# ProtoSnap-LilyTwinkle.net
KiCad netlist of a schematic drawn in EAGLE
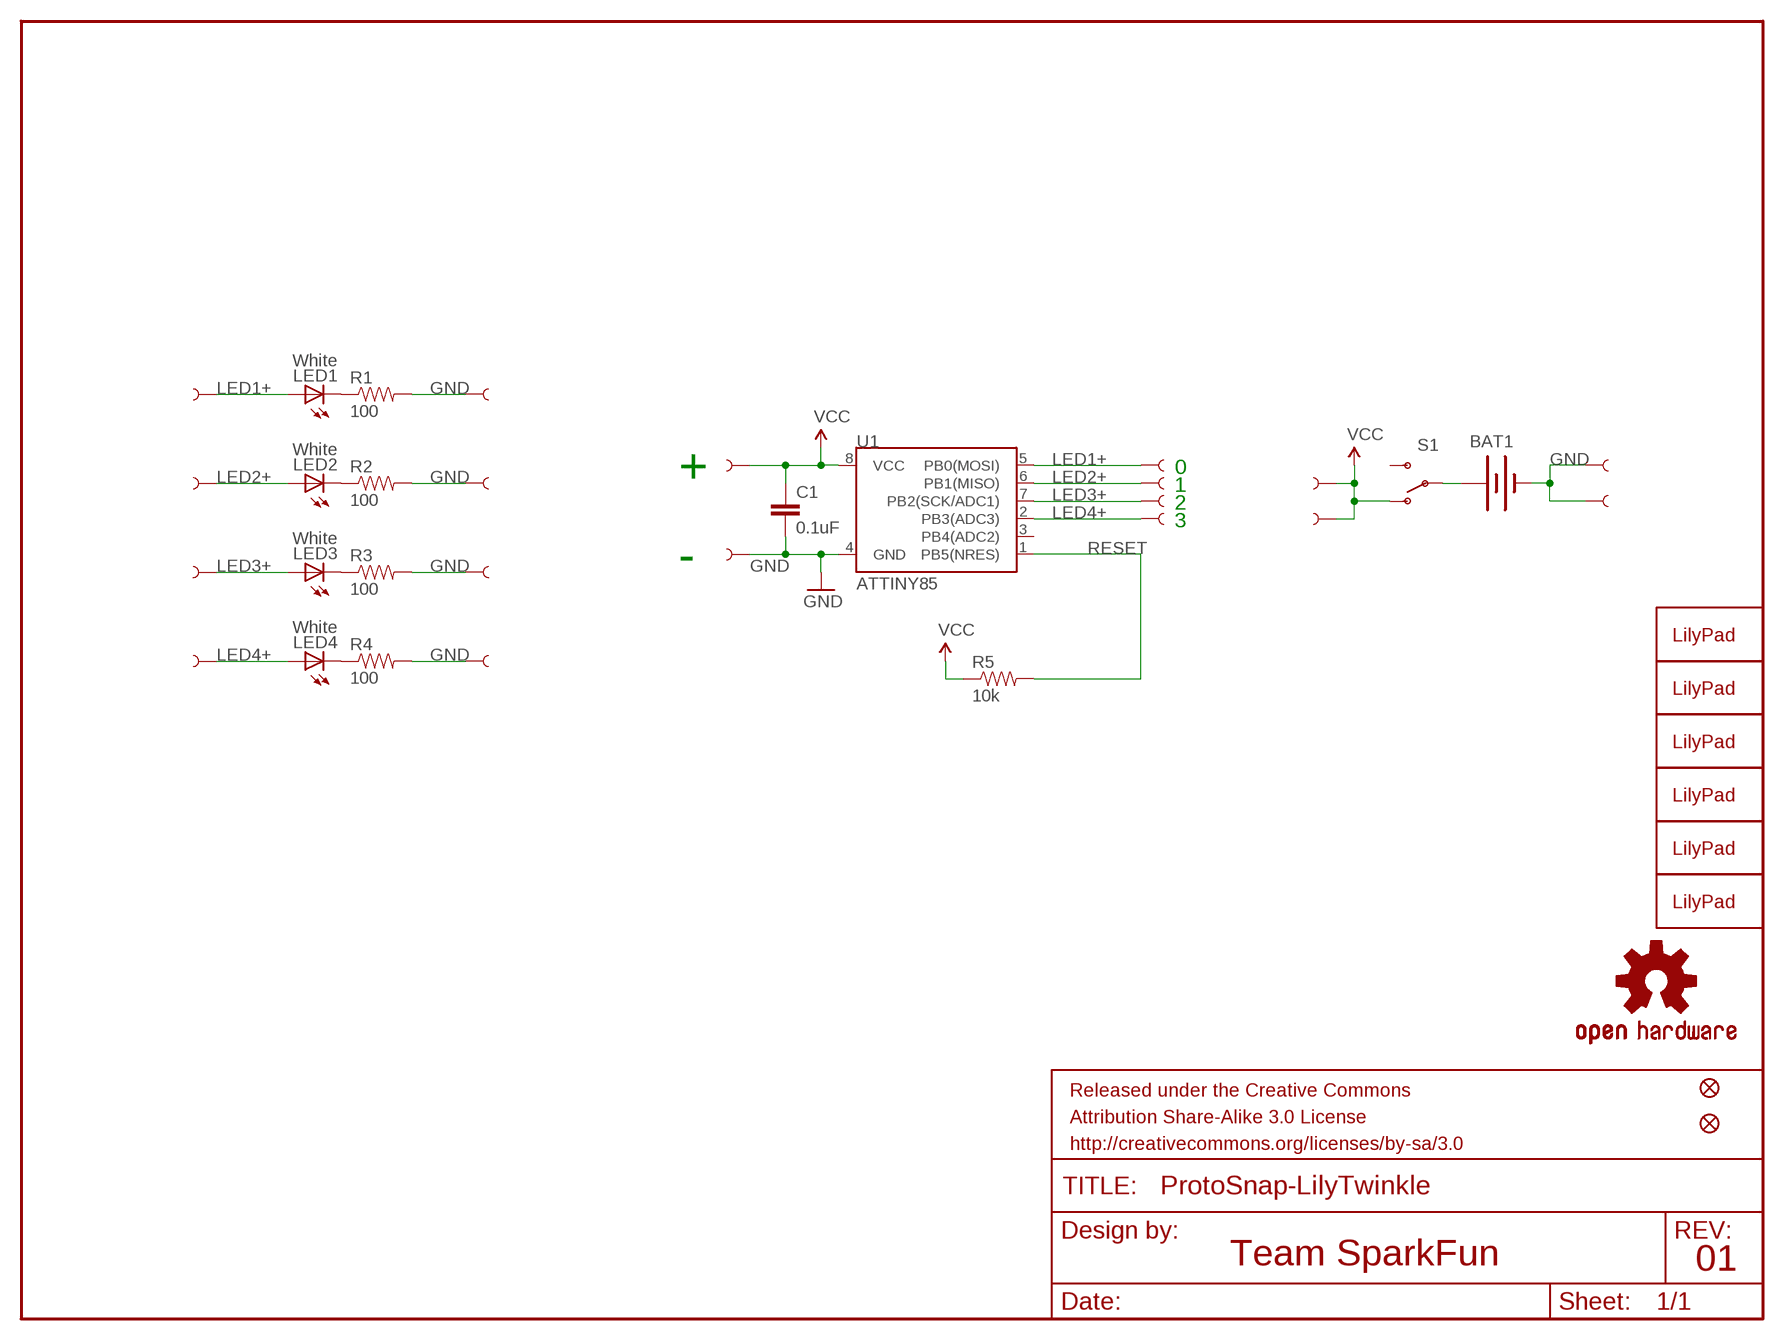
[diagram p0: schematic, sheet 1]

(export (version "E")
  (design (tool "Eeschema 10.0.6"))
  (components
    (comp (ref "1_U$2")
      (value "SEWTAP6")
      (footprint "eagle-import:PETAL-SMALL-2SIDE")
      (libsource (lib "eagle-import") (part "SEWTAP6"))
    )
    (comp (ref "1_U$3")
      (value "SEWTAP6")
      (footprint "eagle-import:PETAL-SMALL-2SIDE")
      (libsource (lib "eagle-import") (part "SEWTAP6"))
    )
    (comp (ref "1_U$4")
      (value "SEWTAP6")
      (footprint "eagle-import:PETAL-SMALL-2SIDE")
      (libsource (lib "eagle-import") (part "SEWTAP6"))
    )
    (comp (ref "1_U$5")
      (value "SEWTAP6")
      (footprint "eagle-import:PETAL-SMALL-2SIDE")
      (libsource (lib "eagle-import") (part "SEWTAP6"))
    )
    (comp (ref "1_U$6")
      (value "SEWTAP6")
      (footprint "eagle-import:PETAL-SMALL-2SIDE")
      (libsource (lib "eagle-import") (part "SEWTAP6"))
    )
    (comp (ref "1_U$7")
      (value "SEWTAP6")
      (footprint "eagle-import:PETAL-SMALL-2SIDE")
      (libsource (lib "eagle-import") (part "SEWTAP6"))
    )
    (comp (ref "3_LED+")
      (value "SEWTAP6")
      (footprint "eagle-import:PETAL-SMALL")
      (libsource (lib "eagle-import") (part "3_LilyPad-Wearables_SEWTAP4"))
    )
    (comp (ref "3_LED-")
      (value "SEWTAP6")
      (footprint "eagle-import:PETAL-SMALL")
      (libsource (lib "eagle-import") (part "SEWTAP2SIDE"))
    )
    (comp (ref "4_LED+")
      (value "SEWTAP6")
      (footprint "eagle-import:PETAL-SMALL")
      (libsource (lib "eagle-import") (part "4_LilyPad-Wearables_SEWTAP4"))
    )
    (comp (ref "4_LED-")
      (value "SEWTAP6")
      (footprint "eagle-import:PETAL-SMALL")
      (libsource (lib "eagle-import") (part "4_LilyPad-Wearables_SEWTAP2SIDE"))
    )
    (comp (ref "5_LED+")
      (value "SEWTAP6")
      (footprint "eagle-import:PETAL-SMALL")
      (libsource (lib "eagle-import") (part "5_LilyPad-Wearables_SEWTAP4"))
    )
    (comp (ref "5_LED-")
      (value "SEWTAP6")
      (footprint "eagle-import:PETAL-SMALL")
      (libsource (lib "eagle-import") (part "5_LilyPad-Wearables_SEWTAP2SIDE"))
    )
    (comp (ref "6_LED+")
      (value "SEWTAP6")
      (footprint "eagle-import:PETAL-SMALL")
      (libsource (lib "eagle-import") (part "6_LilyPad-Wearables_SEWTAP4"))
    )
    (comp (ref "6_LED-")
      (value "SEWTAP6")
      (footprint "eagle-import:PETAL-SMALL")
      (libsource (lib "eagle-import") (part "6_LilyPad-Wearables_SEWTAP2SIDE"))
    )
    (comp (ref "B1+")
      (value "SEWTAP6")
      (footprint "eagle-import:PETAL-SMALL-2SIDE")
      (libsource (lib "eagle-import") (part "2_LilyPad-Wearables_SEWTAP6"))
    )
    (comp (ref "B1-")
      (value "SEWTAP6")
      (footprint "eagle-import:PETAL-SMALL-2SIDE")
      (libsource (lib "eagle-import") (part "2_LilyPad-Wearables_SEWTAP6"))
    )
    (comp (ref "B2+")
      (value "SEWTAP6")
      (footprint "eagle-import:PETAL-SMALL-2SIDE")
      (libsource (lib "eagle-import") (part "2_LilyPad-Wearables_SEWTAP6"))
    )
    (comp (ref "B2-")
      (value "SEWTAP6")
      (footprint "eagle-import:PETAL-SMALL-2SIDE")
      (libsource (lib "eagle-import") (part "2_LilyPad-Wearables_SEWTAP6"))
    )
    (comp (ref "BAT1")
      (value "BATTERY20MM_4LEGS")
      (footprint "eagle-import:BATTCON_20MM_4LEGS")
      (libsource (lib "eagle-import") (part "BATTERY20MM_4LEGS"))
    )
    (comp (ref "BATT_LOGO")
      (value "LOGO-LPLP")
      (footprint "eagle-import:LOGO-LILYPAD")
      (libsource (lib "eagle-import") (part "LOGO-LPLP"))
    )
    (comp (ref "BATT_OHS")
      (value "OSHW-LOGOS")
      (footprint "eagle-import:OSHW-LOGO-S")
      (libsource (lib "eagle-import") (part "OSHW-LOGOS"))
    )
    (comp (ref "C1")
      (value "0.1uF")
      (footprint "eagle-import:0402-CAP")
      (libsource (lib "eagle-import") (part ".1UF-CER"))
    )
    (comp (ref "FRAME1")
      (value "FRAME-LETTER")
      (footprint "eagle-import:CREATIVE_COMMONS")
      (libsource (lib "eagle-import") (part "FRAME-LETTER"))
    )
    (comp (ref "JP1")
      (value "FIDUCIALUFIDUCIAL")
      (footprint "eagle-import:MICRO-FIDUCIAL")
      (libsource (lib "eagle-import") (part "FIDUCIALUFIDUCIAL"))
    )
    (comp (ref "JP2")
      (value "FIDUCIALUFIDUCIAL")
      (footprint "eagle-import:MICRO-FIDUCIAL")
      (libsource (lib "eagle-import") (part "FIDUCIALUFIDUCIAL"))
    )
    (comp (ref "LED1")
      (value "White")
      (footprint "eagle-import:LED-1206")
      (libsource (lib "eagle-import") (part "LED-WHITE"))
    )
    (comp (ref "LED1_LOGO")
      (value "LOGO-LPL")
      (footprint "eagle-import:LOGO-L")
      (libsource (lib "eagle-import") (part "LOGO-LPL"))
    )
    (comp (ref "LED2")
      (value "White")
      (footprint "eagle-import:LED-1206")
      (libsource (lib "eagle-import") (part "LED-WHITE"))
    )
    (comp (ref "LED2_LOGO")
      (value "LOGO-LPL")
      (footprint "eagle-import:LOGO-L")
      (libsource (lib "eagle-import") (part "LOGO-LPL"))
    )
    (comp (ref "LED3")
      (value "White")
      (footprint "eagle-import:LED-1206")
      (libsource (lib "eagle-import") (part "LED-WHITE"))
    )
    (comp (ref "LED3_LOGO")
      (value "LOGO-LPL")
      (footprint "eagle-import:LOGO-L")
      (libsource (lib "eagle-import") (part "LOGO-LPL"))
    )
    (comp (ref "LED4")
      (value "White")
      (footprint "eagle-import:LED-1206")
      (libsource (lib "eagle-import") (part "LED-WHITE"))
    )
    (comp (ref "LED4_LOGO")
      (value "LOGO-LPL")
      (footprint "eagle-import:LOGO-L")
      (libsource (lib "eagle-import") (part "LOGO-LPL"))
    )
    (comp (ref "R1")
      (value "100")
      (footprint "eagle-import:0603-RES")
      (libsource (lib "eagle-import") (part "6_SparkFun_RESISTOR0603-RES"))
    )
    (comp (ref "R2")
      (value "100")
      (footprint "eagle-import:0603-RES")
      (libsource (lib "eagle-import") (part "5_SparkFun_RESISTOR0603-RES"))
    )
    (comp (ref "R3")
      (value "100")
      (footprint "eagle-import:0603-RES")
      (libsource (lib "eagle-import") (part "RESISTOR0603-RES"))
    )
    (comp (ref "R4")
      (value "100")
      (footprint "eagle-import:0603-RES")
      (libsource (lib "eagle-import") (part "4_SparkFun_RESISTOR0603-RES"))
    )
    (comp (ref "R5")
      (value "10k")
      (footprint "eagle-import:0402-RES")
      (libsource (lib "eagle-import") (part "10K-1%RES-00824"))
    )
    (comp (ref "S1")
      (value "SWITCH-SPDTSMD")
      (footprint "eagle-import:AYZ0202")
      (libsource (lib "eagle-import") (part "SWITCH-SPDTSMD"))
    )
    (comp (ref "TINY_LOGO")
      (value "LOGO-LPL")
      (footprint "eagle-import:LOGO-L")
      (libsource (lib "eagle-import") (part "LOGO-LPL"))
    )
    (comp (ref "U1")
      (value "ATTINY85")
      (footprint "eagle-import:SO08-EIAJ")
      (libsource (lib "eagle-import") (part "ATTINY45TINY85-20-SMT"))
    )
  )
  (nets
    (net (code "1") (name "/LED1+") (class "Default")
      (node (ref "1_U$7") (pin "1") (pinfunction "1_1") (pintype "bidirectional"))
      (node (ref "6_LED+") (pin "1") (pinfunction "1_1") (pintype "bidirectional"))
      (node (ref "LED1") (pin "A") (pinfunction "A_A") (pintype "passive"))
      (node (ref "U1") (pin "5") (pinfunction "PB0(MOSI)_5") (pintype "bidirectional"))
    )
    (net (code "2") (name "/LED2+") (class "Default")
      (node (ref "1_U$3") (pin "1") (pinfunction "1_1") (pintype "bidirectional"))
      (node (ref "5_LED+") (pin "1") (pinfunction "1_1") (pintype "bidirectional"))
      (node (ref "LED2") (pin "A") (pinfunction "A_A") (pintype "passive"))
      (node (ref "U1") (pin "6") (pinfunction "PB1(MISO)_6") (pintype "bidirectional"))
    )
    (net (code "3") (name "/LED3+") (class "Default")
      (node (ref "1_U$4") (pin "1") (pinfunction "1_1") (pintype "bidirectional"))
      (node (ref "3_LED+") (pin "1") (pinfunction "1_1") (pintype "bidirectional"))
      (node (ref "LED3") (pin "A") (pinfunction "A_A") (pintype "passive"))
      (node (ref "U1") (pin "7") (pinfunction "PB2(SCK/ADC1)_7") (pintype "bidirectional"))
    )
    (net (code "4") (name "/LED4+") (class "Default")
      (node (ref "1_U$6") (pin "1") (pinfunction "1_1") (pintype "bidirectional"))
      (node (ref "4_LED+") (pin "1") (pinfunction "1_1") (pintype "bidirectional"))
      (node (ref "LED4") (pin "A") (pinfunction "A_A") (pintype "passive"))
      (node (ref "U1") (pin "2") (pinfunction "PB3(ADC3)_2") (pintype "bidirectional"))
    )
    (net (code "5") (name "/RESET") (class "Default")
      (node (ref "R5") (pin "2") (pinfunction "2_2") (pintype "passive"))
      (node (ref "U1") (pin "1") (pinfunction "PB5(NRES)_1") (pintype "bidirectional"))
    )
    (net (code "6") (name "GND") (class "Default")
      (node (ref "1_U$2") (pin "1") (pinfunction "1_1") (pintype "bidirectional"))
      (node (ref "3_LED-") (pin "1") (pinfunction "1_1") (pintype "bidirectional"))
      (node (ref "4_LED-") (pin "1") (pinfunction "1_1") (pintype "bidirectional"))
      (node (ref "5_LED-") (pin "1") (pinfunction "1_1") (pintype "bidirectional"))
      (node (ref "6_LED-") (pin "1") (pinfunction "1_1") (pintype "bidirectional"))
      (node (ref "B1-") (pin "1") (pinfunction "1_1") (pintype "bidirectional"))
      (node (ref "B2-") (pin "1") (pinfunction "1_1") (pintype "bidirectional"))
      (node (ref "BAT1") (pin "2") (pinfunction "-_2") (pintype "power_in"))
      (node (ref "C1") (pin "2") (pinfunction "2_2") (pintype "passive"))
      (node (ref "R1") (pin "2") (pinfunction "2_2") (pintype "passive"))
      (node (ref "R2") (pin "2") (pinfunction "2_2") (pintype "passive"))
      (node (ref "R3") (pin "2") (pinfunction "2_2") (pintype "passive"))
      (node (ref "R4") (pin "2") (pinfunction "2_2") (pintype "passive"))
      (node (ref "U1") (pin "4") (pinfunction "GND_4") (pintype "bidirectional"))
    )
    (net (code "7") (name "Net-(BAT1-+)") (class "Default")
      (node (ref "BAT1") (pin "1") (pinfunction "+_1") (pintype "power_in"))
      (node (ref "S1") (pin "2") (pinfunction "P_2") (pintype "passive"))
    )
    (net (code "8") (name "Net-(LED1-PadC)") (class "Default")
      (node (ref "LED1") (pin "C") (pinfunction "C_C") (pintype "passive"))
      (node (ref "R1") (pin "1") (pinfunction "1_1") (pintype "passive"))
    )
    (net (code "9") (name "Net-(LED2-PadC)") (class "Default")
      (node (ref "LED2") (pin "C") (pinfunction "C_C") (pintype "passive"))
      (node (ref "R2") (pin "1") (pinfunction "1_1") (pintype "passive"))
    )
    (net (code "10") (name "Net-(LED3-PadC)") (class "Default")
      (node (ref "LED3") (pin "C") (pinfunction "C_C") (pintype "passive"))
      (node (ref "R3") (pin "1") (pinfunction "1_1") (pintype "passive"))
    )
    (net (code "11") (name "Net-(LED4-PadC)") (class "Default")
      (node (ref "LED4") (pin "C") (pinfunction "C_C") (pintype "passive"))
      (node (ref "R4") (pin "1") (pinfunction "1_1") (pintype "passive"))
    )
    (net (code "12") (name "VCC") (class "Default")
      (node (ref "1_U$5") (pin "1") (pinfunction "1_1") (pintype "bidirectional"))
      (node (ref "B1+") (pin "1") (pinfunction "1_1") (pintype "bidirectional"))
      (node (ref "B2+") (pin "1") (pinfunction "1_1") (pintype "bidirectional"))
      (node (ref "C1") (pin "1") (pinfunction "1_1") (pintype "passive"))
      (node (ref "R5") (pin "1") (pinfunction "1_1") (pintype "passive"))
      (node (ref "S1") (pin "1") (pinfunction "O_1") (pintype "passive"))
      (node (ref "U1") (pin "8") (pinfunction "VCC_8") (pintype "bidirectional"))
    )
    (net (code "13") (name "unconnected-(S1-S-Pad3)") (class "Default")
      (node (ref "S1") (pin "3") (pinfunction "S_3") (pintype "passive"))
    )
    (net (code "14") (name "unconnected-(U1-PB4(ADC2)-Pad3)") (class "Default")
      (node (ref "U1") (pin "3") (pinfunction "PB4(ADC2)_3") (pintype "bidirectional"))
    )
  )
)
